# msp430g2955.net
KiCad netlist of a schematic drawn in EAGLE
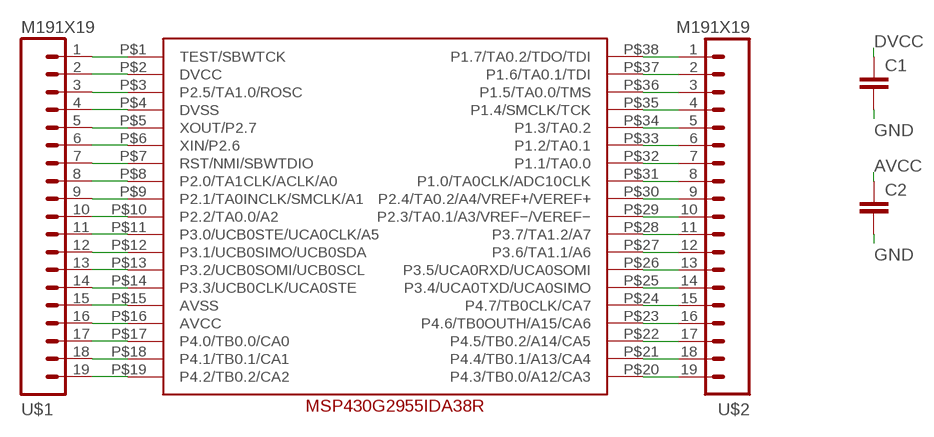
[diagram p0: schematic, sheet 1]

(export (version "E")
  (design (tool "Eeschema 10.0.6"))
  (components
    (comp (ref "C1")
      (value "C-EUC0805")
      (footprint "eagle-import:C0805")
      (libsource (lib "eagle-import") (part "C-EUC0805"))
    )
    (comp (ref "C2")
      (value "C-EUC0805")
      (footprint "eagle-import:C0805")
      (libsource (lib "eagle-import") (part "C-EUC0805"))
    )
    (comp (ref "U$1")
      (value "M191X19")
      (footprint "eagle-import:1X19")
      (libsource (lib "eagle-import") (part "M191X19"))
    )
    (comp (ref "U$2")
      (value "M191X19")
      (footprint "eagle-import:1X19")
      (libsource (lib "eagle-import") (part "M191X19"))
    )
    (comp (ref "U$3")
      (value "MSP430G2955IDA38R")
      (footprint "eagle-import:MSP430G2955IDA38R")
      (libsource (lib "eagle-import") (part "MSP430G2955IDA38R"))
    )
  )
  (nets
    (net (code "1") (name "/AVCC") (class "Default")
      (node (ref "C2") (pin "1") (pinfunction "1_1") (pintype "passive"))
      (node (ref "U$1") (pin "16") (pinfunction "16_16") (pintype "passive"))
      (node (ref "U$3") (pin "P$16") (pinfunction "AVCC_P$16") (pintype "bidirectional"))
    )
    (net (code "2") (name "/DVCC") (class "Default")
      (node (ref "C1") (pin "1") (pinfunction "1_1") (pintype "passive"))
      (node (ref "U$1") (pin "2") (pinfunction "2_2") (pintype "passive"))
      (node (ref "U$3") (pin "P$2") (pinfunction "DVCC_P$2") (pintype "bidirectional"))
    )
    (net (code "3") (name "/GND") (class "Default")
      (node (ref "C1") (pin "2") (pinfunction "2_2") (pintype "passive"))
      (node (ref "C2") (pin "2") (pinfunction "2_2") (pintype "passive"))
      (node (ref "U$1") (pin "15") (pinfunction "15_15") (pintype "passive"))
      (node (ref "U$1") (pin "4") (pinfunction "4_4") (pintype "passive"))
      (node (ref "U$3") (pin "P$15") (pinfunction "AVSS_P$15") (pintype "bidirectional"))
      (node (ref "U$3") (pin "P$4") (pinfunction "DVSS_P$4") (pintype "bidirectional"))
    )
    (net (code "4") (name "Net-(U$3-P1.0{slash}TA0CLK{slash}ADC10CLK)") (class "Default")
      (node (ref "U$2") (pin "8") (pinfunction "8_8") (pintype "passive"))
      (node (ref "U$3") (pin "P$31") (pinfunction "P1.0/TA0CLK/ADC10CLK_P$31") (pintype "bidirectional"))
    )
    (net (code "5") (name "Net-(U$3-P1.1{slash}TA0.0)") (class "Default")
      (node (ref "U$2") (pin "7") (pinfunction "7_7") (pintype "passive"))
      (node (ref "U$3") (pin "P$32") (pinfunction "P1.1/TA0.0_P$32") (pintype "bidirectional"))
    )
    (net (code "6") (name "Net-(U$3-P1.2{slash}TA0.1)") (class "Default")
      (node (ref "U$2") (pin "6") (pinfunction "6_6") (pintype "passive"))
      (node (ref "U$3") (pin "P$33") (pinfunction "P1.2/TA0.1_P$33") (pintype "bidirectional"))
    )
    (net (code "7") (name "Net-(U$3-P1.3{slash}TA0.2)") (class "Default")
      (node (ref "U$2") (pin "5") (pinfunction "5_5") (pintype "passive"))
      (node (ref "U$3") (pin "P$34") (pinfunction "P1.3/TA0.2_P$34") (pintype "bidirectional"))
    )
    (net (code "8") (name "Net-(U$3-P1.4{slash}SMCLK{slash}TCK)") (class "Default")
      (node (ref "U$2") (pin "4") (pinfunction "4_4") (pintype "passive"))
      (node (ref "U$3") (pin "P$35") (pinfunction "P1.4/SMCLK/TCK_P$35") (pintype "bidirectional"))
    )
    (net (code "9") (name "Net-(U$3-P1.5{slash}TA0.0{slash}TMS)") (class "Default")
      (node (ref "U$2") (pin "3") (pinfunction "3_3") (pintype "passive"))
      (node (ref "U$3") (pin "P$36") (pinfunction "P1.5/TA0.0/TMS_P$36") (pintype "bidirectional"))
    )
    (net (code "10") (name "Net-(U$3-P1.6{slash}TA0.1{slash}TDI)") (class "Default")
      (node (ref "U$2") (pin "2") (pinfunction "2_2") (pintype "passive"))
      (node (ref "U$3") (pin "P$37") (pinfunction "P1.6/TA0.1/TDI_P$37") (pintype "bidirectional"))
    )
    (net (code "11") (name "Net-(U$3-P1.7{slash}TA0.2{slash}TDO{slash}TDI)") (class "Default")
      (node (ref "U$2") (pin "1") (pinfunction "1_1") (pintype "passive"))
      (node (ref "U$3") (pin "P$38") (pinfunction "P1.7/TA0.2/TDO/TDI_P$38") (pintype "bidirectional"))
    )
    (net (code "12") (name "Net-(U$3-P2.0{slash}TA1CLK{slash}ACLK{slash}A0)") (class "Default")
      (node (ref "U$1") (pin "8") (pinfunction "8_8") (pintype "passive"))
      (node (ref "U$3") (pin "P$8") (pinfunction "P2.0/TA1CLK/ACLK/A0_P$8") (pintype "bidirectional"))
    )
    (net (code "13") (name "Net-(U$3-P2.1{slash}TA0INCLK{slash}SMCLK{slash}A1)") (class "Default")
      (node (ref "U$1") (pin "9") (pinfunction "9_9") (pintype "passive"))
      (node (ref "U$3") (pin "P$9") (pinfunction "P2.1/TA0INCLK/SMCLK/A1_P$9") (pintype "bidirectional"))
    )
    (net (code "14") (name "Net-(U$3-P2.2{slash}TA0.0{slash}A2)") (class "Default")
      (node (ref "U$1") (pin "10") (pinfunction "10_10") (pintype "passive"))
      (node (ref "U$3") (pin "P$10") (pinfunction "P2.2/TA0.0/A2_P$10") (pintype "bidirectional"))
    )
    (net (code "15") (name "Net-(U$3-P2.3{slash}TA0.1{slash}A3{slash}VREF−{slash}VEREF−)") (class "Default")
      (node (ref "U$2") (pin "10") (pinfunction "10_10") (pintype "passive"))
      (node (ref "U$3") (pin "P$29") (pinfunction "P2.3/TA0.1/A3/VREF−/VEREF−_P$29") (pintype "bidirectional"))
    )
    (net (code "16") (name "Net-(U$3-P2.4{slash}TA0.2{slash}A4{slash}VREF+{slash}VEREF+)") (class "Default")
      (node (ref "U$2") (pin "9") (pinfunction "9_9") (pintype "passive"))
      (node (ref "U$3") (pin "P$30") (pinfunction "P2.4/TA0.2/A4/VREF+/VEREF+_P$30") (pintype "bidirectional"))
    )
    (net (code "17") (name "Net-(U$3-P2.5{slash}TA1.0{slash}ROSC)") (class "Default")
      (node (ref "U$1") (pin "3") (pinfunction "3_3") (pintype "passive"))
      (node (ref "U$3") (pin "P$3") (pinfunction "P2.5/TA1.0/ROSC_P$3") (pintype "bidirectional"))
    )
    (net (code "18") (name "Net-(U$3-P3.0{slash}UCB0STE{slash}UCA0CLK{slash}A5)") (class "Default")
      (node (ref "U$1") (pin "11") (pinfunction "11_11") (pintype "passive"))
      (node (ref "U$3") (pin "P$11") (pinfunction "P3.0/UCB0STE/UCA0CLK/A5_P$11") (pintype "bidirectional"))
    )
    (net (code "19") (name "Net-(U$3-P3.1{slash}UCB0SIMO{slash}UCB0SDA)") (class "Default")
      (node (ref "U$1") (pin "12") (pinfunction "12_12") (pintype "passive"))
      (node (ref "U$3") (pin "P$12") (pinfunction "P3.1/UCB0SIMO/UCB0SDA_P$12") (pintype "bidirectional"))
    )
    (net (code "20") (name "Net-(U$3-P3.2{slash}UCB0SOMI{slash}UCB0SCL)") (class "Default")
      (node (ref "U$1") (pin "13") (pinfunction "13_13") (pintype "passive"))
      (node (ref "U$3") (pin "P$13") (pinfunction "P3.2/UCB0SOMI/UCB0SCL_P$13") (pintype "bidirectional"))
    )
    (net (code "21") (name "Net-(U$3-P3.3{slash}UCB0CLK{slash}UCA0STE)") (class "Default")
      (node (ref "U$1") (pin "14") (pinfunction "14_14") (pintype "passive"))
      (node (ref "U$3") (pin "P$14") (pinfunction "P3.3/UCB0CLK/UCA0STE_P$14") (pintype "bidirectional"))
    )
    (net (code "22") (name "Net-(U$3-P3.4{slash}UCA0TXD{slash}UCA0SIMO)") (class "Default")
      (node (ref "U$2") (pin "14") (pinfunction "14_14") (pintype "passive"))
      (node (ref "U$3") (pin "P$25") (pinfunction "P3.4/UCA0TXD/UCA0SIMO_P$25") (pintype "bidirectional"))
    )
    (net (code "23") (name "Net-(U$3-P3.5{slash}UCA0RXD{slash}UCA0SOMI)") (class "Default")
      (node (ref "U$2") (pin "13") (pinfunction "13_13") (pintype "passive"))
      (node (ref "U$3") (pin "P$26") (pinfunction "P3.5/UCA0RXD/UCA0SOMI_P$26") (pintype "bidirectional"))
    )
    (net (code "24") (name "Net-(U$3-P3.6{slash}TA1.1{slash}A6)") (class "Default")
      (node (ref "U$2") (pin "12") (pinfunction "12_12") (pintype "passive"))
      (node (ref "U$3") (pin "P$27") (pinfunction "P3.6/TA1.1/A6_P$27") (pintype "bidirectional"))
    )
    (net (code "25") (name "Net-(U$3-P3.7{slash}TA1.2{slash}A7)") (class "Default")
      (node (ref "U$2") (pin "11") (pinfunction "11_11") (pintype "passive"))
      (node (ref "U$3") (pin "P$28") (pinfunction "P3.7/TA1.2/A7_P$28") (pintype "bidirectional"))
    )
    (net (code "26") (name "Net-(U$3-P4.0{slash}TB0.0{slash}CA0)") (class "Default")
      (node (ref "U$1") (pin "17") (pinfunction "17_17") (pintype "passive"))
      (node (ref "U$3") (pin "P$17") (pinfunction "P4.0/TB0.0/CA0_P$17") (pintype "bidirectional"))
    )
    (net (code "27") (name "Net-(U$3-P4.1{slash}TB0.1{slash}CA1)") (class "Default")
      (node (ref "U$1") (pin "18") (pinfunction "18_18") (pintype "passive"))
      (node (ref "U$3") (pin "P$18") (pinfunction "P4.1/TB0.1/CA1_P$18") (pintype "bidirectional"))
    )
    (net (code "28") (name "Net-(U$3-P4.2{slash}TB0.2{slash}CA2)") (class "Default")
      (node (ref "U$1") (pin "19") (pinfunction "19_19") (pintype "passive"))
      (node (ref "U$3") (pin "P$19") (pinfunction "P4.2/TB0.2/CA2_P$19") (pintype "bidirectional"))
    )
    (net (code "29") (name "Net-(U$3-P4.3{slash}TB0.0{slash}A12{slash}CA3)") (class "Default")
      (node (ref "U$2") (pin "19") (pinfunction "19_19") (pintype "passive"))
      (node (ref "U$3") (pin "P$20") (pinfunction "P4.3/TB0.0/A12/CA3_P$20") (pintype "bidirectional"))
    )
    (net (code "30") (name "Net-(U$3-P4.4{slash}TB0.1{slash}A13{slash}CA4)") (class "Default")
      (node (ref "U$2") (pin "18") (pinfunction "18_18") (pintype "passive"))
      (node (ref "U$3") (pin "P$21") (pinfunction "P4.4/TB0.1/A13/CA4_P$21") (pintype "bidirectional"))
    )
    (net (code "31") (name "Net-(U$3-P4.5{slash}TB0.2{slash}A14{slash}CA5)") (class "Default")
      (node (ref "U$2") (pin "17") (pinfunction "17_17") (pintype "passive"))
      (node (ref "U$3") (pin "P$22") (pinfunction "P4.5/TB0.2/A14/CA5_P$22") (pintype "bidirectional"))
    )
    (net (code "32") (name "Net-(U$3-P4.6{slash}TB0OUTH{slash}A15{slash}CA6)") (class "Default")
      (node (ref "U$2") (pin "16") (pinfunction "16_16") (pintype "passive"))
      (node (ref "U$3") (pin "P$23") (pinfunction "P4.6/TB0OUTH/A15/CA6_P$23") (pintype "bidirectional"))
    )
    (net (code "33") (name "Net-(U$3-P4.7{slash}TB0CLK{slash}CA7)") (class "Default")
      (node (ref "U$2") (pin "15") (pinfunction "15_15") (pintype "passive"))
      (node (ref "U$3") (pin "P$24") (pinfunction "P4.7/TB0CLK/CA7_P$24") (pintype "bidirectional"))
    )
    (net (code "34") (name "Net-(U$3-RST{slash}NMI{slash}SBWTDIO)") (class "Default")
      (node (ref "U$1") (pin "7") (pinfunction "7_7") (pintype "passive"))
      (node (ref "U$3") (pin "P$7") (pinfunction "RST/NMI/SBWTDIO_P$7") (pintype "bidirectional"))
    )
    (net (code "35") (name "Net-(U$3-TEST{slash}SBWTCK)") (class "Default")
      (node (ref "U$1") (pin "1") (pinfunction "1_1") (pintype "passive"))
      (node (ref "U$3") (pin "P$1") (pinfunction "TEST/SBWTCK_P$1") (pintype "bidirectional"))
    )
    (net (code "36") (name "Net-(U$3-XIN{slash}P2.6)") (class "Default")
      (node (ref "U$1") (pin "6") (pinfunction "6_6") (pintype "passive"))
      (node (ref "U$3") (pin "P$6") (pinfunction "XIN/P2.6_P$6") (pintype "bidirectional"))
    )
    (net (code "37") (name "Net-(U$3-XOUT{slash}P2.7)") (class "Default")
      (node (ref "U$1") (pin "5") (pinfunction "5_5") (pintype "passive"))
      (node (ref "U$3") (pin "P$5") (pinfunction "XOUT/P2.7_P$5") (pintype "bidirectional"))
    )
  )
)
